# RC_mux_157.net
KiCad netlist of a schematic drawn in EAGLE
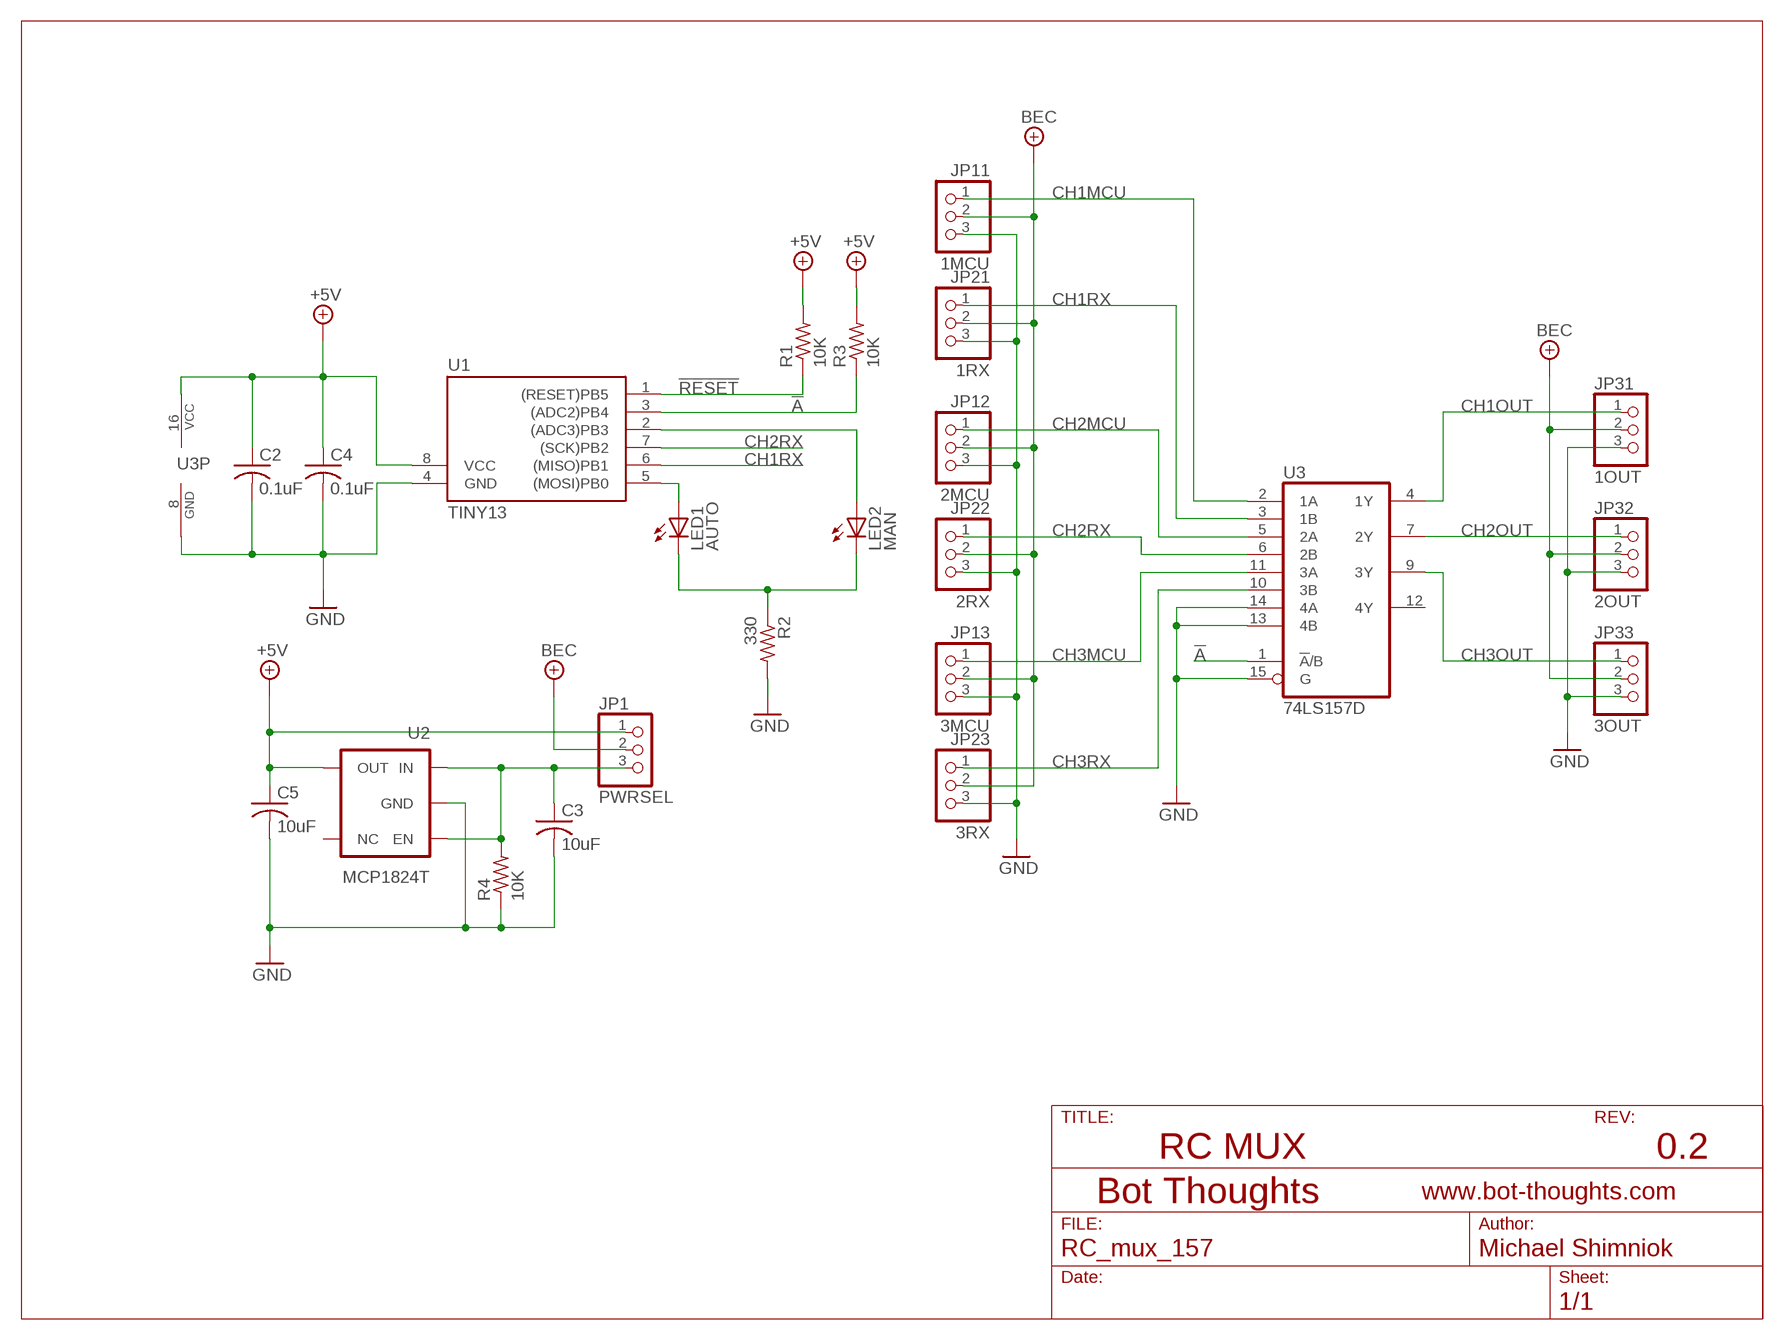
[diagram p0: schematic, sheet 1]

(export (version "E")
  (design (tool "Eeschema 10.0.6"))
  (components
    (comp (ref "C2")
      (value "0.1uF")
      (footprint "eagle-import:C0603")
      (fields (field (name "PARTNO") "C1608X7R1E104K080AA"))
      (libsource (lib "eagle-import") (part "C-USC0603"))
    )
    (comp (ref "C3")
      (value "10uF")
      (footprint "eagle-import:C0603")
      (fields (field (name "PARTNO") "CL10A106MP8NNNC"))
      (libsource (lib "eagle-import") (part "C-USC0603"))
    )
    (comp (ref "C4")
      (value "0.1uF")
      (footprint "eagle-import:C0603")
      (fields (field (name "PARTNO") "C1608X7R1E104K080AA"))
      (libsource (lib "eagle-import") (part "C-USC0603"))
    )
    (comp (ref "C5")
      (value "10uF")
      (footprint "eagle-import:C0603")
      (fields (field (name "PARTNO") "CL10A106MP8NNNC"))
      (libsource (lib "eagle-import") (part "C-USC0603"))
    )
    (comp (ref "JP1")
      (value "PWRSEL")
      (footprint "eagle-import:1X03M")
      (libsource (lib "eagle-import") (part "PINHD-1X03_2.00"))
    )
    (comp (ref "JP11")
      (value "1MCU")
      (footprint "eagle-import:1X03-S")
      (libsource (lib "eagle-import") (part "PINHD-1X03_2.54-S"))
    )
    (comp (ref "JP12")
      (value "2MCU")
      (footprint "eagle-import:1X03-S")
      (libsource (lib "eagle-import") (part "PINHD-1X03_2.54-S"))
    )
    (comp (ref "JP13")
      (value "3MCU")
      (footprint "eagle-import:1X03-S")
      (libsource (lib "eagle-import") (part "PINHD-1X03_2.54-S"))
    )
    (comp (ref "JP21")
      (value "1RX")
      (footprint "eagle-import:1X03-S")
      (libsource (lib "eagle-import") (part "PINHD-1X03_2.54-S"))
    )
    (comp (ref "JP22")
      (value "2RX")
      (footprint "eagle-import:1X03-S")
      (libsource (lib "eagle-import") (part "PINHD-1X03_2.54-S"))
    )
    (comp (ref "JP23")
      (value "3RX")
      (footprint "eagle-import:1X03-S")
      (libsource (lib "eagle-import") (part "PINHD-1X03_2.54-S"))
    )
    (comp (ref "JP31")
      (value "1OUT")
      (footprint "eagle-import:1X03-S")
      (libsource (lib "eagle-import") (part "PINHD-1X03_2.54-S"))
    )
    (comp (ref "JP32")
      (value "2OUT")
      (footprint "eagle-import:1X03-S")
      (libsource (lib "eagle-import") (part "PINHD-1X03_2.54-S"))
    )
    (comp (ref "JP33")
      (value "3OUT")
      (footprint "eagle-import:1X03-S")
      (libsource (lib "eagle-import") (part "PINHD-1X03_2.54-S"))
    )
    (comp (ref "LED1")
      (value "AUTO")
      (footprint "eagle-import:CHIPLED_1206")
      (fields (field (name "PARTNO") "LH N974-KN-1"))
      (libsource (lib "eagle-import") (part "LEDCHIPLED_1206"))
    )
    (comp (ref "LED2")
      (value "MAN")
      (footprint "eagle-import:CHIPLED_1206")
      (fields (field (name "PARTNO") "LG N971-KN-1"))
      (libsource (lib "eagle-import") (part "LEDCHIPLED_1206"))
    )
    (comp (ref "R1")
      (value "10K")
      (footprint "eagle-import:R0603")
      (fields (field (name "PARTNO") "1622829-1"))
      (libsource (lib "eagle-import") (part "R-US_R0603"))
    )
    (comp (ref "R2")
      (value "330")
      (footprint "eagle-import:R0603")
      (fields (field (name "PARTNO") "RC0603JR-07330RL"))
      (libsource (lib "eagle-import") (part "R-US_R0603"))
    )
    (comp (ref "R3")
      (value "10K")
      (footprint "eagle-import:R0603")
      (fields (field (name "PARTNO") "1622829-1"))
      (libsource (lib "eagle-import") (part "R-US_R0603"))
    )
    (comp (ref "R4")
      (value "10K")
      (footprint "eagle-import:R0603")
      (fields (field (name "PARTNO") "1622829-1"))
      (libsource (lib "eagle-import") (part "R-US_R0603"))
    )
    (comp (ref "U1")
      (value "TINY13")
      (footprint "eagle-import:SO08")
      (fields (field (name "PARTNO") "ATTINY13A-SSH"))
      (libsource (lib "eagle-import") (part "TINY138S2"))
    )
    (comp (ref "U2")
      (value "MCP1824T")
      (footprint "eagle-import:SOT23-5")
      (fields (field (name "PARTNO") "MCP1824T-5002E/OT"))
      (libsource (lib "eagle-import") (part "MCP1801"))
    )
    (comp (ref "U3")
      (value "74LS157D")
      (footprint "eagle-import:SO16")
      (fields (field (name "PARTNO") "74HCT157D,652"))
      (libsource (lib "eagle-import") (part "74157DLS"))
    )
  )
  (nets
    (net (code "1") (name "+5V") (class "Default")
      (node (ref "C2") (pin "1") (pinfunction "1_1") (pintype "passive"))
      (node (ref "C4") (pin "1") (pinfunction "1_1") (pintype "passive"))
      (node (ref "C5") (pin "1") (pinfunction "1_1") (pintype "passive"))
      (node (ref "JP1") (pin "1") (pinfunction "1_1") (pintype "passive"))
      (node (ref "R1") (pin "2") (pinfunction "2_2") (pintype "passive"))
      (node (ref "R3") (pin "2") (pinfunction "2_2") (pintype "passive"))
      (node (ref "U1") (pin "8") (pinfunction "VCC_8") (pintype "power_in"))
      (node (ref "U2") (pin "5") (pinfunction "OUT_5") (pintype "passive"))
      (node (ref "U3") (pin "16") (pinfunction "VCC_16") (pintype "power_in"))
    )
    (net (code "2") (name "/CH1MCU") (class "Default")
      (node (ref "JP11") (pin "1") (pinfunction "1_1") (pintype "passive"))
      (node (ref "U3") (pin "2") (pinfunction "1A_2") (pintype "input"))
    )
    (net (code "3") (name "/CH1OUT") (class "Default")
      (node (ref "JP31") (pin "1") (pinfunction "1_1") (pintype "passive"))
      (node (ref "U3") (pin "4") (pinfunction "1Y_4") (pintype "output"))
    )
    (net (code "4") (name "/CH1RX") (class "Default")
      (node (ref "JP21") (pin "1") (pinfunction "1_1") (pintype "passive"))
      (node (ref "U1") (pin "6") (pinfunction "(MISO)PB1_6") (pintype "bidirectional"))
      (node (ref "U3") (pin "3") (pinfunction "1B_3") (pintype "input"))
    )
    (net (code "5") (name "/CH2MCU") (class "Default")
      (node (ref "JP12") (pin "1") (pinfunction "1_1") (pintype "passive"))
      (node (ref "U3") (pin "5") (pinfunction "2A_5") (pintype "input"))
    )
    (net (code "6") (name "/CH2OUT") (class "Default")
      (node (ref "JP32") (pin "1") (pinfunction "1_1") (pintype "passive"))
      (node (ref "U3") (pin "7") (pinfunction "2Y_7") (pintype "output"))
    )
    (net (code "7") (name "/CH2RX") (class "Default")
      (node (ref "JP22") (pin "1") (pinfunction "1_1") (pintype "passive"))
      (node (ref "U1") (pin "7") (pinfunction "(SCK)PB2_7") (pintype "bidirectional"))
      (node (ref "U3") (pin "6") (pinfunction "2B_6") (pintype "input"))
    )
    (net (code "8") (name "/CH3MCU") (class "Default")
      (node (ref "JP13") (pin "1") (pinfunction "1_1") (pintype "passive"))
      (node (ref "U3") (pin "11") (pinfunction "3A_11") (pintype "input"))
    )
    (net (code "9") (name "/CH3OUT") (class "Default")
      (node (ref "JP33") (pin "1") (pinfunction "1_1") (pintype "passive"))
      (node (ref "U3") (pin "9") (pinfunction "3Y_9") (pintype "output"))
    )
    (net (code "10") (name "/CH3RX") (class "Default")
      (node (ref "JP23") (pin "1") (pinfunction "1_1") (pintype "passive"))
      (node (ref "U3") (pin "10") (pinfunction "3B_10") (pintype "input"))
    )
    (net (code "11") (name "/~{A}") (class "Default")
      (node (ref "R3") (pin "1") (pinfunction "1_1") (pintype "passive"))
      (node (ref "U1") (pin "3") (pinfunction "(ADC2)PB4_3") (pintype "bidirectional"))
      (node (ref "U3") (pin "1") (pinfunction "~{A}/B_1") (pintype "input"))
    )
    (net (code "12") (name "/~{RESET}") (class "Default")
      (node (ref "R1") (pin "1") (pinfunction "1_1") (pintype "passive"))
      (node (ref "U1") (pin "1") (pinfunction "(RESET)PB5_1") (pintype "bidirectional"))
    )
    (net (code "13") (name "BEC") (class "Default")
      (node (ref "JP1") (pin "2") (pinfunction "2_2") (pintype "passive"))
      (node (ref "JP11") (pin "2") (pinfunction "2_2") (pintype "passive"))
      (node (ref "JP12") (pin "2") (pinfunction "2_2") (pintype "passive"))
      (node (ref "JP13") (pin "2") (pinfunction "2_2") (pintype "passive"))
      (node (ref "JP21") (pin "2") (pinfunction "2_2") (pintype "passive"))
      (node (ref "JP22") (pin "2") (pinfunction "2_2") (pintype "passive"))
      (node (ref "JP23") (pin "2") (pinfunction "2_2") (pintype "passive"))
      (node (ref "JP31") (pin "2") (pinfunction "2_2") (pintype "passive"))
      (node (ref "JP32") (pin "2") (pinfunction "2_2") (pintype "passive"))
      (node (ref "JP33") (pin "2") (pinfunction "2_2") (pintype "passive"))
    )
    (net (code "14") (name "GND") (class "Default")
      (node (ref "C2") (pin "2") (pinfunction "2_2") (pintype "passive"))
      (node (ref "C3") (pin "2") (pinfunction "2_2") (pintype "passive"))
      (node (ref "C4") (pin "2") (pinfunction "2_2") (pintype "passive"))
      (node (ref "C5") (pin "2") (pinfunction "2_2") (pintype "passive"))
      (node (ref "JP11") (pin "3") (pinfunction "3_3") (pintype "passive"))
      (node (ref "JP12") (pin "3") (pinfunction "3_3") (pintype "passive"))
      (node (ref "JP13") (pin "3") (pinfunction "3_3") (pintype "passive"))
      (node (ref "JP21") (pin "3") (pinfunction "3_3") (pintype "passive"))
      (node (ref "JP22") (pin "3") (pinfunction "3_3") (pintype "passive"))
      (node (ref "JP23") (pin "3") (pinfunction "3_3") (pintype "passive"))
      (node (ref "JP31") (pin "3") (pinfunction "3_3") (pintype "passive"))
      (node (ref "JP32") (pin "3") (pinfunction "3_3") (pintype "passive"))
      (node (ref "JP33") (pin "3") (pinfunction "3_3") (pintype "passive"))
      (node (ref "R2") (pin "2") (pinfunction "2_2") (pintype "passive"))
      (node (ref "R4") (pin "1") (pinfunction "1_1") (pintype "passive"))
      (node (ref "U1") (pin "4") (pinfunction "GND_4") (pintype "power_in"))
      (node (ref "U2") (pin "2") (pinfunction "GND_2") (pintype "input"))
      (node (ref "U3") (pin "13") (pinfunction "4B_13") (pintype "input"))
      (node (ref "U3") (pin "14") (pinfunction "4A_14") (pintype "input"))
      (node (ref "U3") (pin "15") (pinfunction "G_15") (pintype "input"))
      (node (ref "U3") (pin "8") (pinfunction "GND_8") (pintype "power_in"))
    )
    (net (code "15") (name "Net-(LED1-PadC)") (class "Default")
      (node (ref "LED1") (pin "C") (pinfunction "C_C") (pintype "passive"))
      (node (ref "LED2") (pin "C") (pinfunction "C_C") (pintype "passive"))
      (node (ref "R2") (pin "1") (pinfunction "1_1") (pintype "passive"))
    )
    (net (code "16") (name "Net-(U1-(ADC3)PB3)") (class "Default")
      (node (ref "LED2") (pin "A") (pinfunction "A_A") (pintype "passive"))
      (node (ref "U1") (pin "2") (pinfunction "(ADC3)PB3_2") (pintype "bidirectional"))
    )
    (net (code "17") (name "Net-(U1-(MOSI)PB0)") (class "Default")
      (node (ref "LED1") (pin "A") (pinfunction "A_A") (pintype "passive"))
      (node (ref "U1") (pin "5") (pinfunction "(MOSI)PB0_5") (pintype "bidirectional"))
    )
    (net (code "18") (name "Net-(U2-EN)") (class "Default")
      (node (ref "C3") (pin "1") (pinfunction "1_1") (pintype "passive"))
      (node (ref "JP1") (pin "3") (pinfunction "3_3") (pintype "passive"))
      (node (ref "R4") (pin "2") (pinfunction "2_2") (pintype "passive"))
      (node (ref "U2") (pin "1") (pinfunction "IN_1") (pintype "input"))
      (node (ref "U2") (pin "3") (pinfunction "EN_3") (pintype "input"))
    )
    (net (code "19") (name "unconnected-(U2-NC-Pad4)") (class "Default")
      (node (ref "U2") (pin "4") (pinfunction "NC_4") (pintype "input"))
    )
    (net (code "20") (name "unconnected-(U3A-4Y-Pad12)") (class "Default")
      (node (ref "U3") (pin "12") (pinfunction "4Y_12") (pintype "output"))
    )
  )
)
